# SCH_Thermoblock.net
KiCad netlist of a schematic drawn in EasyEDA
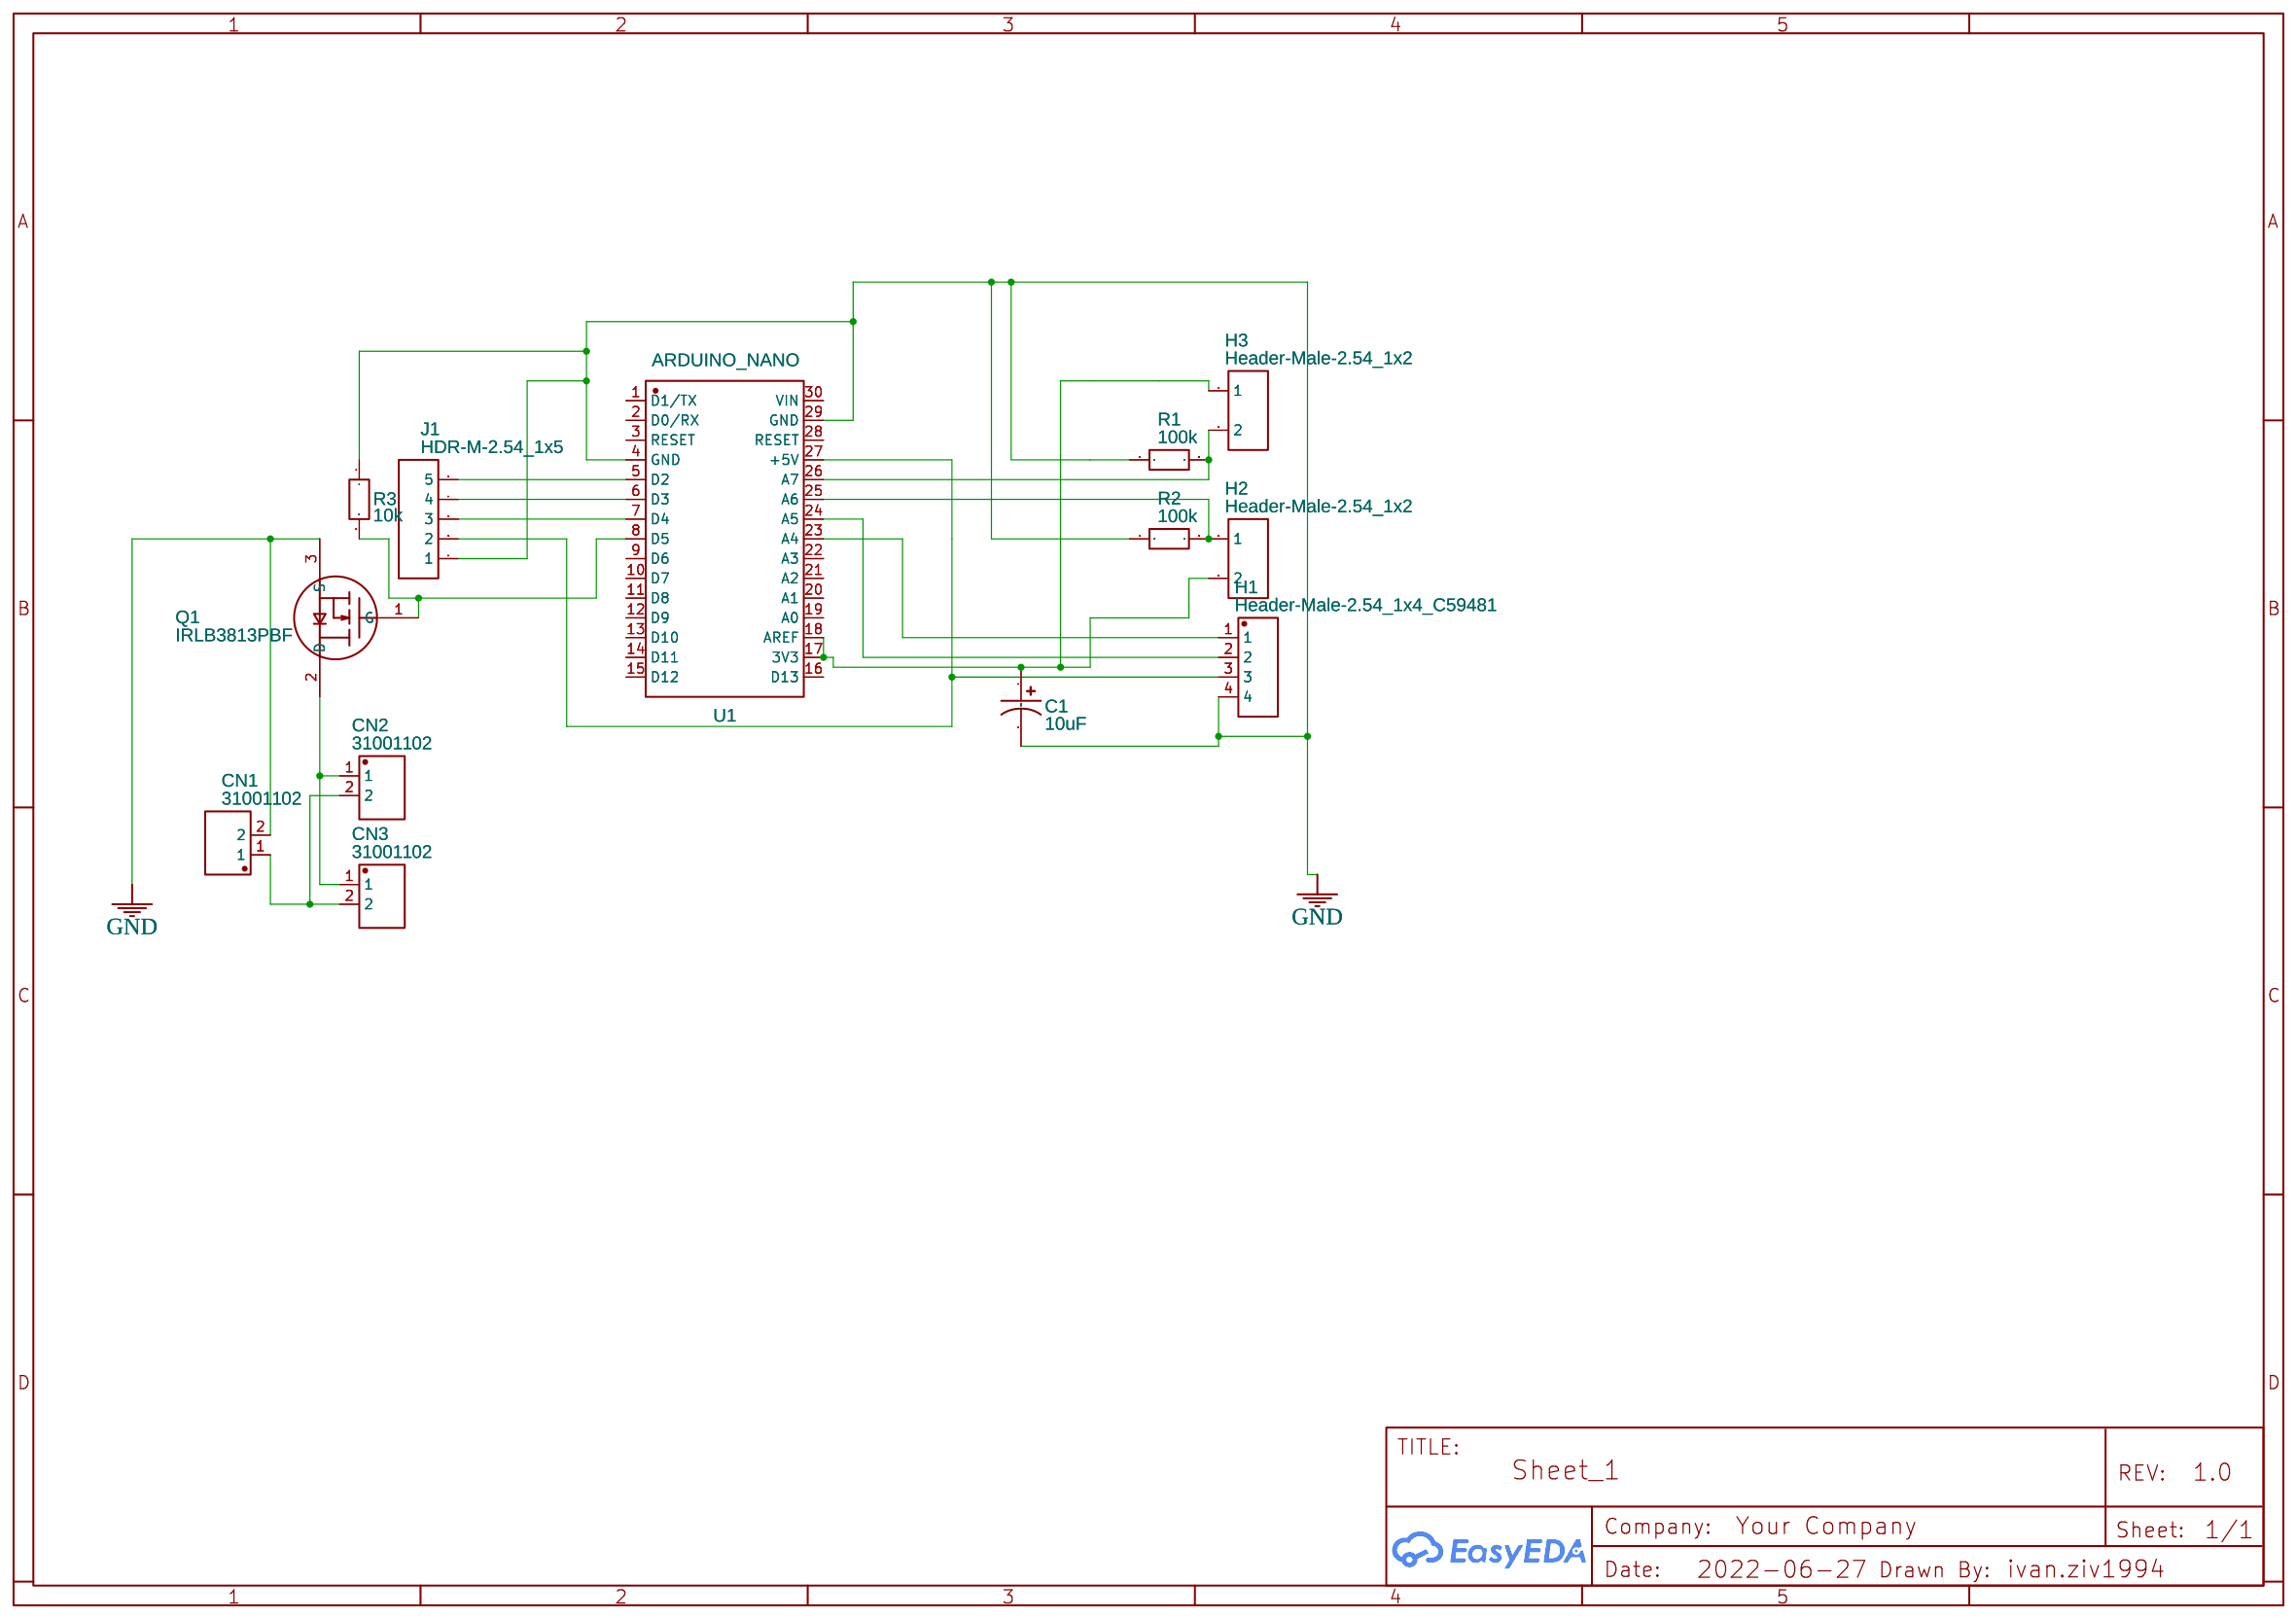
[diagram p0: schematic sheet]

(export (version "E")
  (design (tool "Eeschema 10.0.6"))
  (components
    (comp (ref "C1") (value "10uF") (libsource (lib "") (part "CE_TH_D5.0×F2.0_US")))
    (comp (ref "CN1")
      (value "31001102")
      (fields (field (name "BOM_Supplier Part") "C123210"))
      (libsource (lib "") (part "31001102"))
    )
    (comp (ref "CN2")
      (value "31001102")
      (fields (field (name "BOM_Supplier Part") "C123210"))
      (libsource (lib "") (part "31001102_1"))
    )
    (comp (ref "CN3")
      (value "31001102")
      (fields (field (name "BOM_Supplier Part") "C123210"))
      (libsource (lib "") (part "31001102_1"))
    )
    (comp (ref "H1")
      (value "Header-Male-2.54_1x4_C59481")
      (fields
        (field (name "BOM_Manufacturer Part") "Headers  Pins 1*4P")
        (field (name "BOM_Supplier Part") "C59481")
      )
      (libsource (lib "") (part "Header-Male-2.54_1x4_C59481"))
    )
    (comp (ref "H2")
      (value "Header-Male-2.54_1x2")
      (fields (field (name "BOM_Manufacturer Part") "826629-2") (field (name "BOM_Supplier Part") "C86471"))
      (libsource (lib "") (part "Header-Male-2.54_1x2"))
    )
    (comp (ref "H3")
      (value "Header-Male-2.54_1x2")
      (fields (field (name "BOM_Manufacturer Part") "826629-2") (field (name "BOM_Supplier Part") "C86471"))
      (libsource (lib "") (part "Header-Male-2.54_1x2"))
    )
    (comp (ref "J1")
      (value "HDR-M-2.54_1x5")
      (fields (field (name "BOM_Supplier Part") "C358687"))
      (libsource (lib "") (part "HDR-M-2.54_1x5"))
    )
    (comp (ref "Q1")
      (value "IRLB3813PBF")
      (fields (field (name "BOM_Supplier Part") "C148140"))
      (libsource (lib "") (part "IRLB3813PBF"))
    )
    (comp (ref "R1") (value "100k") (libsource (lib "") (part "R_AXIAL-0.4_EU")))
    (comp (ref "R2") (value "100k") (libsource (lib "") (part "R_AXIAL-0.4_EU")))
    (comp (ref "R3") (value "10k") (libsource (lib "") (part "R_AXIAL-0.4_EU_1")))
    (comp (ref "U1")
      (value "ARDUINO_NANO")
      (fields (field (name "BOM_Supplier Part") "C9900017879"))
      (libsource (lib "") (part "ARDUINO_NANO"))
    )
  )
  (nets
    (net (code "1") (name "GND") (class "Default")
      (node (ref "C1") (pin "2") (pinfunction "2_2") (pintype "unspecified"))
      (node (ref "CN1") (pin "2") (pinfunction "2_2") (pintype "unspecified"))
      (node (ref "H1") (pin "4") (pinfunction "4_4") (pintype "unspecified"))
      (node (ref "J1") (pin "1") (pinfunction "1_1") (pintype "unspecified"))
      (node (ref "Q1") (pin "3") (pinfunction "S_3") (pintype "unspecified"))
      (node (ref "R1") (pin "1") (pinfunction "1_1") (pintype "unspecified"))
      (node (ref "R2") (pin "1") (pinfunction "1_1") (pintype "unspecified"))
      (node (ref "R3") (pin "1") (pinfunction "1_1") (pintype "unspecified"))
      (node (ref "U1") (pin "29") (pinfunction "GND_29") (pintype "unspecified"))
      (node (ref "U1") (pin "4") (pinfunction "GND_4") (pintype "unspecified"))
    )
    (net (code "2") (name "Net-(CN1-Pad1)") (class "Default")
      (node (ref "CN1") (pin "1") (pinfunction "1_1") (pintype "unspecified"))
      (node (ref "CN2") (pin "2") (pinfunction "2_2") (pintype "unspecified"))
      (node (ref "CN3") (pin "2") (pinfunction "2_2") (pintype "unspecified"))
    )
    (net (code "3") (name "Net-(Q1-D)") (class "Default")
      (node (ref "CN2") (pin "1") (pinfunction "1_1") (pintype "unspecified"))
      (node (ref "CN3") (pin "1") (pinfunction "1_1") (pintype "unspecified"))
      (node (ref "Q1") (pin "2") (pinfunction "D_2") (pintype "unspecified"))
    )
    (net (code "4") (name "Net-(Q1-G)") (class "Default")
      (node (ref "Q1") (pin "1") (pinfunction "G_1") (pintype "unspecified"))
      (node (ref "R3") (pin "2") (pinfunction "2_2") (pintype "unspecified"))
      (node (ref "U1") (pin "8") (pinfunction "D5_8") (pintype "unspecified"))
    )
    (net (code "5") (name "Net-(U1-+5V)") (class "Default")
      (node (ref "H1") (pin "3") (pinfunction "3_3") (pintype "unspecified"))
      (node (ref "J1") (pin "2") (pinfunction "2_2") (pintype "unspecified"))
      (node (ref "U1") (pin "27") (pinfunction "+5V_27") (pintype "unspecified"))
    )
    (net (code "6") (name "Net-(U1-3V3)") (class "Default")
      (node (ref "C1") (pin "1") (pinfunction "1_1") (pintype "unspecified"))
      (node (ref "H2") (pin "2") (pinfunction "2_2") (pintype "unspecified"))
      (node (ref "H3") (pin "1") (pinfunction "1_1") (pintype "unspecified"))
      (node (ref "U1") (pin "17") (pinfunction "3V3_17") (pintype "unspecified"))
      (node (ref "U1") (pin "18") (pinfunction "AREF_18") (pintype "unspecified"))
    )
    (net (code "7") (name "Net-(U1-A4)") (class "Default")
      (node (ref "H1") (pin "1") (pinfunction "1_1") (pintype "unspecified"))
      (node (ref "U1") (pin "23") (pinfunction "A4_23") (pintype "unspecified"))
    )
    (net (code "8") (name "Net-(U1-A5)") (class "Default")
      (node (ref "H1") (pin "2") (pinfunction "2_2") (pintype "unspecified"))
      (node (ref "U1") (pin "24") (pinfunction "A5_24") (pintype "unspecified"))
    )
    (net (code "9") (name "Net-(U1-A6)") (class "Default")
      (node (ref "H2") (pin "1") (pinfunction "1_1") (pintype "unspecified"))
      (node (ref "R2") (pin "2") (pinfunction "2_2") (pintype "unspecified"))
      (node (ref "U1") (pin "25") (pinfunction "A6_25") (pintype "unspecified"))
    )
    (net (code "10") (name "Net-(U1-A7)") (class "Default")
      (node (ref "H3") (pin "2") (pinfunction "2_2") (pintype "unspecified"))
      (node (ref "R1") (pin "2") (pinfunction "2_2") (pintype "unspecified"))
      (node (ref "U1") (pin "26") (pinfunction "A7_26") (pintype "unspecified"))
    )
    (net (code "11") (name "Net-(U1-D2)") (class "Default")
      (node (ref "J1") (pin "5") (pinfunction "5_5") (pintype "unspecified"))
      (node (ref "U1") (pin "5") (pinfunction "D2_5") (pintype "unspecified"))
    )
    (net (code "12") (name "Net-(U1-D3)") (class "Default")
      (node (ref "J1") (pin "4") (pinfunction "4_4") (pintype "unspecified"))
      (node (ref "U1") (pin "6") (pinfunction "D3_6") (pintype "unspecified"))
    )
    (net (code "13") (name "Net-(U1-D4)") (class "Default")
      (node (ref "J1") (pin "3") (pinfunction "3_3") (pintype "unspecified"))
      (node (ref "U1") (pin "7") (pinfunction "D4_7") (pintype "unspecified"))
    )
    (net (code "14") (name "unconnected-(U1-A0-Pad19)") (class "Default")
      (node (ref "U1") (pin "19") (pinfunction "A0_19") (pintype "unspecified"))
    )
    (net (code "15") (name "unconnected-(U1-A1-Pad20)") (class "Default")
      (node (ref "U1") (pin "20") (pinfunction "A1_20") (pintype "unspecified"))
    )
    (net (code "16") (name "unconnected-(U1-A2-Pad21)") (class "Default")
      (node (ref "U1") (pin "21") (pinfunction "A2_21") (pintype "unspecified"))
    )
    (net (code "17") (name "unconnected-(U1-A3-Pad22)") (class "Default")
      (node (ref "U1") (pin "22") (pinfunction "A3_22") (pintype "unspecified"))
    )
    (net (code "18") (name "unconnected-(U1-D0{slash}RX-Pad2)") (class "Default")
      (node (ref "U1") (pin "2") (pinfunction "D0/RX_2") (pintype "unspecified"))
    )
    (net (code "19") (name "unconnected-(U1-D1{slash}TX-Pad1)") (class "Default")
      (node (ref "U1") (pin "1") (pinfunction "D1/TX_1") (pintype "unspecified"))
    )
    (net (code "20") (name "unconnected-(U1-D6-Pad9)") (class "Default")
      (node (ref "U1") (pin "9") (pinfunction "D6_9") (pintype "unspecified"))
    )
    (net (code "21") (name "unconnected-(U1-D7-Pad10)") (class "Default")
      (node (ref "U1") (pin "10") (pinfunction "D7_10") (pintype "unspecified"))
    )
    (net (code "22") (name "unconnected-(U1-D8-Pad11)") (class "Default")
      (node (ref "U1") (pin "11") (pinfunction "D8_11") (pintype "unspecified"))
    )
    (net (code "23") (name "unconnected-(U1-D9-Pad12)") (class "Default")
      (node (ref "U1") (pin "12") (pinfunction "D9_12") (pintype "unspecified"))
    )
    (net (code "24") (name "unconnected-(U1-D10-Pad13)") (class "Default")
      (node (ref "U1") (pin "13") (pinfunction "D10_13") (pintype "unspecified"))
    )
    (net (code "25") (name "unconnected-(U1-D11-Pad14)") (class "Default")
      (node (ref "U1") (pin "14") (pinfunction "D11_14") (pintype "unspecified"))
    )
    (net (code "26") (name "unconnected-(U1-D12-Pad15)") (class "Default")
      (node (ref "U1") (pin "15") (pinfunction "D12_15") (pintype "unspecified"))
    )
    (net (code "27") (name "unconnected-(U1-D13-Pad16)") (class "Default")
      (node (ref "U1") (pin "16") (pinfunction "D13_16") (pintype "unspecified"))
    )
    (net (code "28") (name "unconnected-(U1-RESET-Pad3)") (class "Default")
      (node (ref "U1") (pin "3") (pinfunction "RESET_3") (pintype "unspecified"))
    )
    (net (code "29") (name "unconnected-(U1-RESET-Pad28)") (class "Default")
      (node (ref "U1") (pin "28") (pinfunction "RESET_28") (pintype "unspecified"))
    )
    (net (code "30") (name "unconnected-(U1-VIN-Pad30)") (class "Default")
      (node (ref "U1") (pin "30") (pinfunction "VIN_30") (pintype "unspecified"))
    )
  )
)
